# Sheet1.net
KiCad netlist of a schematic drawn in Altium Designer
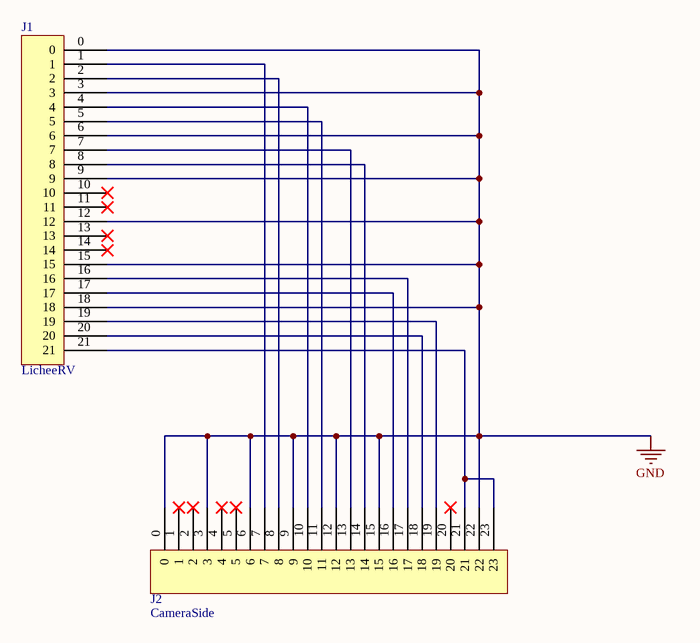
[diagram p0: Sheet1.SchDoc]

(export (version "E")
  (design (tool "Eeschema 10.0.6"))
  (components
    (comp (ref "J1") (value "LicheeRV") (footprint "Nano") (libsource (lib "Lib") (part "LicheeRV")))
    (comp (ref "J2") (value "CameraSide") (footprint "Camera") (libsource (lib "Lib") (part "CameraSide_1")))
  )
  (nets
    (net (code "1") (name "GND") (class "Default")
      (node (ref "J1") (pin "0") (pinfunction "0_0") (pintype "passive"))
      (node (ref "J1") (pin "12") (pinfunction "12_12") (pintype "passive"))
      (node (ref "J1") (pin "15") (pinfunction "15_15") (pintype "passive"))
      (node (ref "J1") (pin "18") (pinfunction "18_18") (pintype "passive"))
      (node (ref "J1") (pin "3") (pinfunction "3_3") (pintype "passive"))
      (node (ref "J1") (pin "6") (pinfunction "6_6") (pintype "passive"))
      (node (ref "J1") (pin "9") (pinfunction "9_9") (pintype "passive"))
      (node (ref "J2") (pin "0") (pinfunction "0_0") (pintype "passive"))
      (node (ref "J2") (pin "12") (pinfunction "12_12") (pintype "passive"))
      (node (ref "J2") (pin "15") (pinfunction "15_15") (pintype "passive"))
      (node (ref "J2") (pin "22") (pinfunction "22_22") (pintype "passive"))
      (node (ref "J2") (pin "3") (pinfunction "3_3") (pintype "passive"))
      (node (ref "J2") (pin "6") (pinfunction "6_6") (pintype "passive"))
      (node (ref "J2") (pin "9") (pinfunction "9_9") (pintype "passive"))
    )
    (net (code "2") (name "Net-(J1-Pad1)") (class "Default")
      (node (ref "J1") (pin "1") (pinfunction "1_1") (pintype "passive"))
      (node (ref "J2") (pin "7") (pinfunction "7_7") (pintype "passive"))
    )
    (net (code "3") (name "Net-(J1-Pad2)") (class "Default")
      (node (ref "J1") (pin "2") (pinfunction "2_2") (pintype "passive"))
      (node (ref "J2") (pin "8") (pinfunction "8_8") (pintype "passive"))
    )
    (net (code "4") (name "Net-(J1-Pad4)") (class "Default")
      (node (ref "J1") (pin "4") (pinfunction "4_4") (pintype "passive"))
      (node (ref "J2") (pin "10") (pinfunction "10_10") (pintype "passive"))
    )
    (net (code "5") (name "Net-(J1-Pad5)") (class "Default")
      (node (ref "J1") (pin "5") (pinfunction "5_5") (pintype "passive"))
      (node (ref "J2") (pin "11") (pinfunction "11_11") (pintype "passive"))
    )
    (net (code "6") (name "Net-(J1-Pad7)") (class "Default")
      (node (ref "J1") (pin "7") (pinfunction "7_7") (pintype "passive"))
      (node (ref "J2") (pin "13") (pinfunction "13_13") (pintype "passive"))
    )
    (net (code "7") (name "Net-(J1-Pad8)") (class "Default")
      (node (ref "J1") (pin "8") (pinfunction "8_8") (pintype "passive"))
      (node (ref "J2") (pin "14") (pinfunction "14_14") (pintype "passive"))
    )
    (net (code "8") (name "Net-(J1-Pad16)") (class "Default")
      (node (ref "J1") (pin "16") (pinfunction "16_16") (pintype "passive"))
      (node (ref "J2") (pin "17") (pinfunction "17_17") (pintype "passive"))
    )
    (net (code "9") (name "Net-(J1-Pad17)") (class "Default")
      (node (ref "J1") (pin "17") (pinfunction "17_17") (pintype "passive"))
      (node (ref "J2") (pin "16") (pinfunction "16_16") (pintype "passive"))
    )
    (net (code "10") (name "Net-(J1-Pad19)") (class "Default")
      (node (ref "J1") (pin "19") (pinfunction "19_19") (pintype "passive"))
      (node (ref "J2") (pin "19") (pinfunction "19_19") (pintype "passive"))
    )
    (net (code "11") (name "Net-(J1-Pad20)") (class "Default")
      (node (ref "J1") (pin "20") (pinfunction "20_20") (pintype "passive"))
      (node (ref "J2") (pin "18") (pinfunction "18_18") (pintype "passive"))
    )
    (net (code "12") (name "Net-(J1-Pad21)") (class "Default")
      (node (ref "J1") (pin "21") (pinfunction "21_21") (pintype "passive"))
      (node (ref "J2") (pin "21") (pinfunction "21_21") (pintype "passive"))
      (node (ref "J2") (pin "23") (pinfunction "23_23") (pintype "passive"))
    )
    (net (code "13") (name "unconnected-(J1-Pad10)") (class "Default")
      (node (ref "J1") (pin "10") (pinfunction "10_10") (pintype "passive+no_connect"))
    )
    (net (code "14") (name "unconnected-(J1-Pad11)") (class "Default")
      (node (ref "J1") (pin "11") (pinfunction "11_11") (pintype "passive+no_connect"))
    )
    (net (code "15") (name "unconnected-(J1-Pad13)") (class "Default")
      (node (ref "J1") (pin "13") (pinfunction "13_13") (pintype "passive+no_connect"))
    )
    (net (code "16") (name "unconnected-(J1-Pad14)") (class "Default")
      (node (ref "J1") (pin "14") (pinfunction "14_14") (pintype "passive+no_connect"))
    )
    (net (code "17") (name "unconnected-(J2-Pad1)") (class "Default")
      (node (ref "J2") (pin "1") (pinfunction "1_1") (pintype "passive+no_connect"))
    )
    (net (code "18") (name "unconnected-(J2-Pad2)") (class "Default")
      (node (ref "J2") (pin "2") (pinfunction "2_2") (pintype "passive+no_connect"))
    )
    (net (code "19") (name "unconnected-(J2-Pad4)") (class "Default")
      (node (ref "J2") (pin "4") (pinfunction "4_4") (pintype "passive+no_connect"))
    )
    (net (code "20") (name "unconnected-(J2-Pad5)") (class "Default")
      (node (ref "J2") (pin "5") (pinfunction "5_5") (pintype "passive+no_connect"))
    )
    (net (code "21") (name "unconnected-(J2-Pad20)") (class "Default")
      (node (ref "J2") (pin "20") (pinfunction "20_20") (pintype "passive+no_connect"))
    )
  )
)
